# SheetMain.net
KiCad netlist of a schematic drawn in Altium Designer
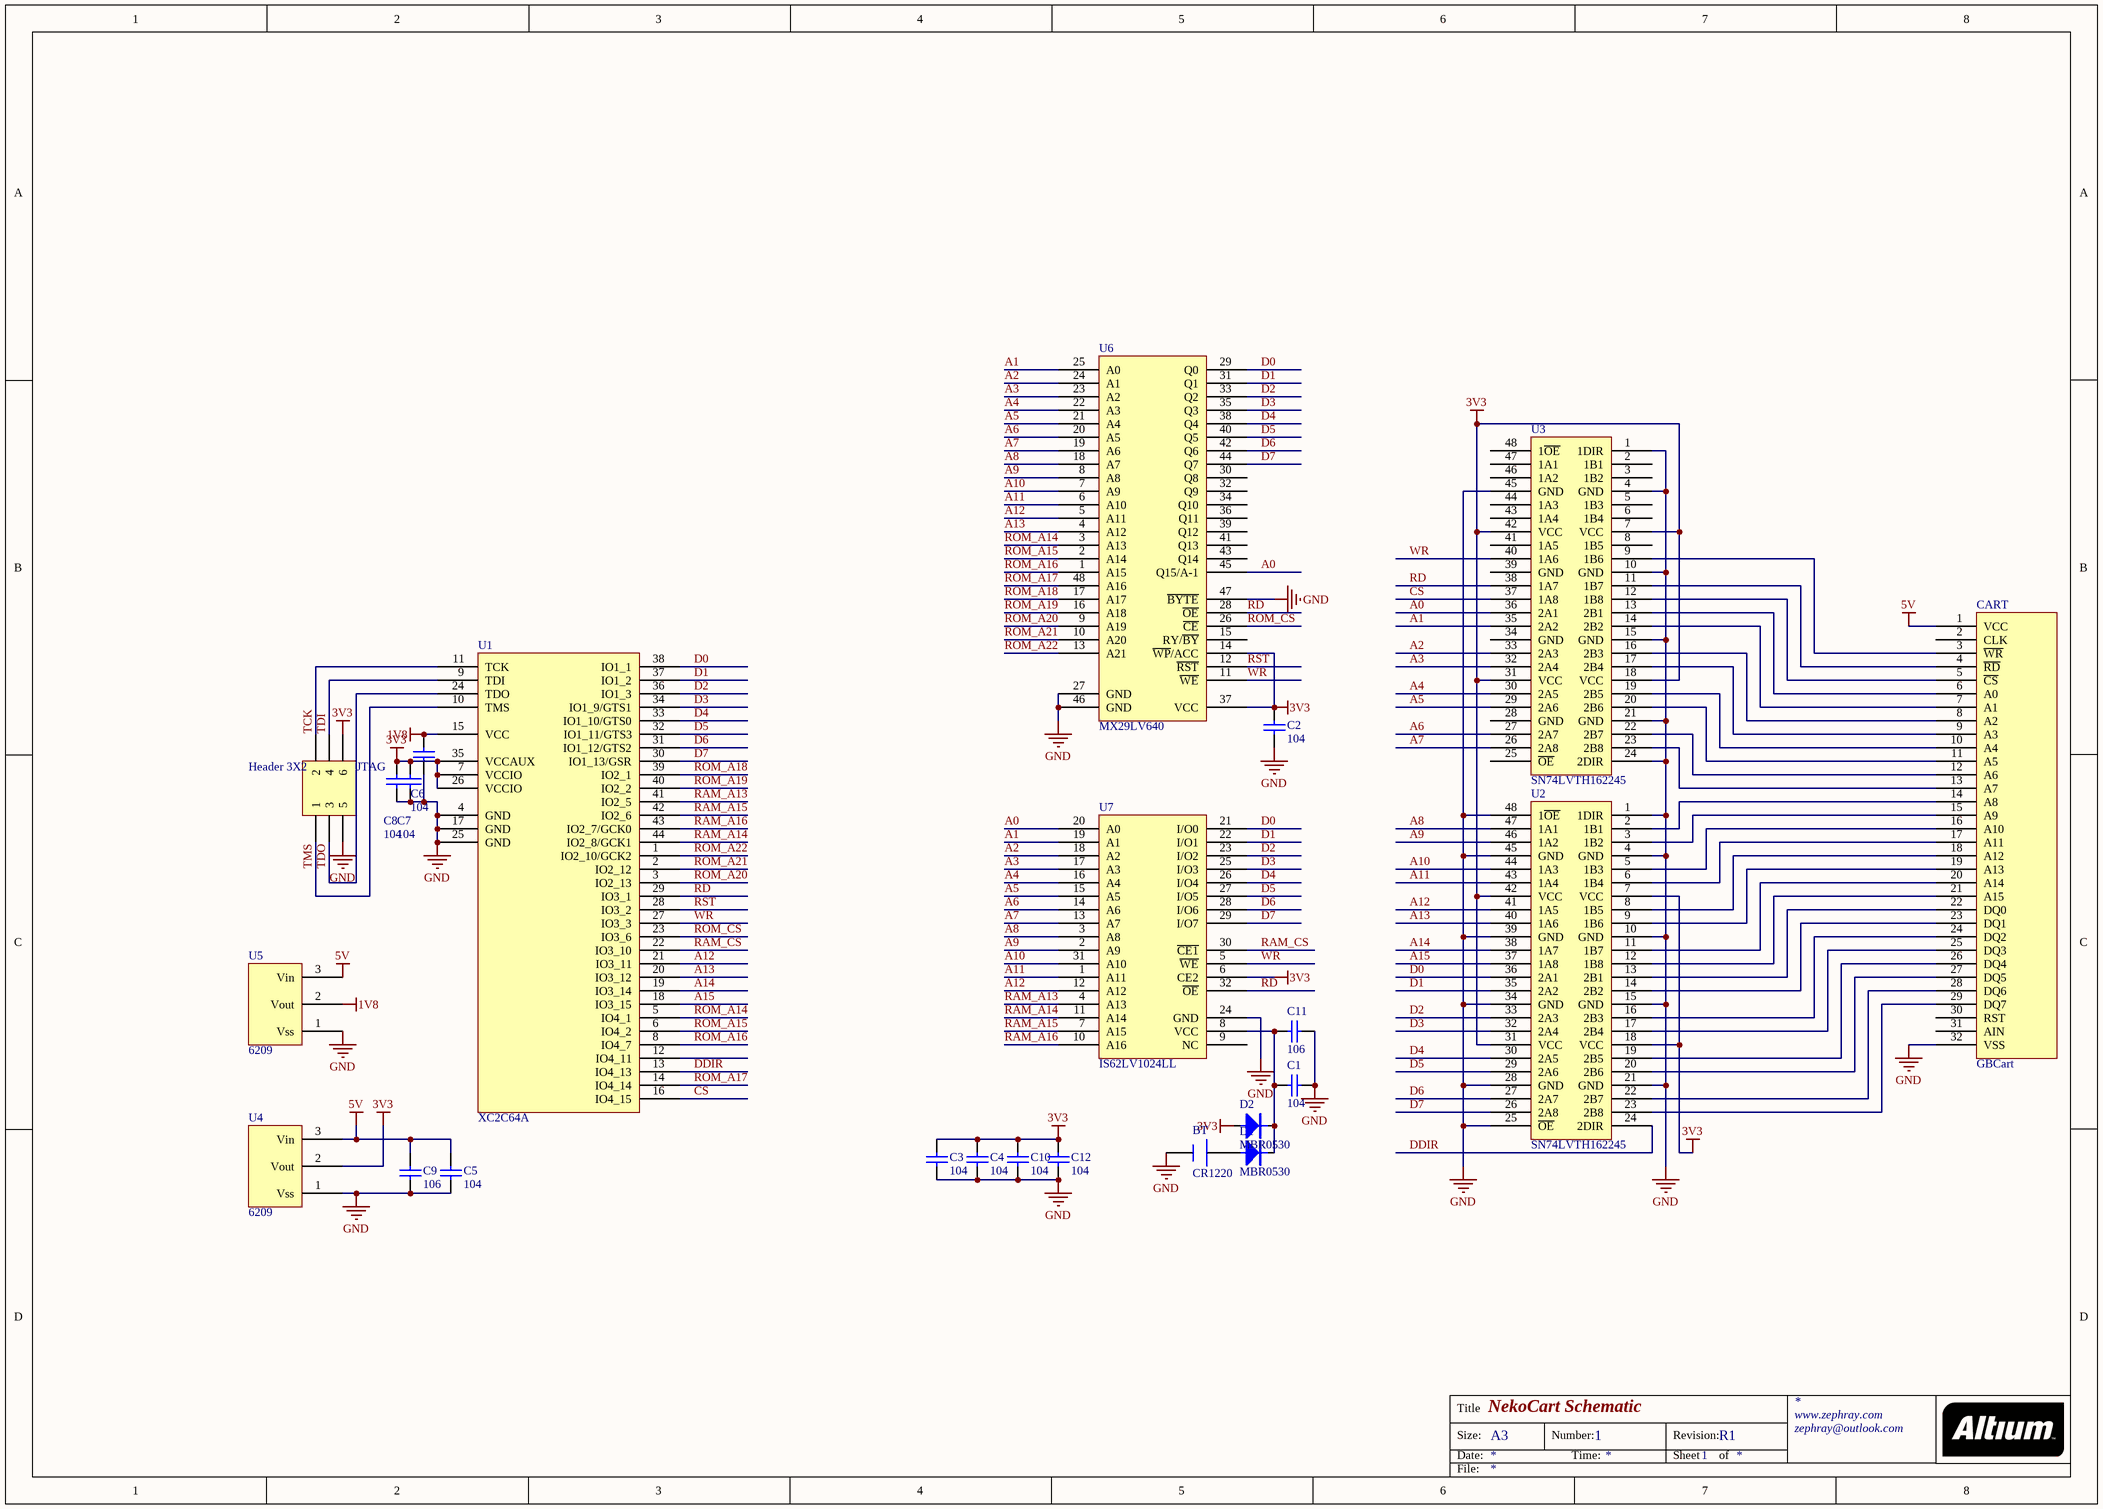
[diagram p0: SheetMain.SchDoc]

(export (version "E")
  (design (tool "Eeschema 10.0.6"))
  (components
    (comp (ref "BT")
      (value "CR1220")
      (footprint "CR1220_socket")
      (fields (field (name "PUBLISHER") "Altium Limited"))
      (libsource (lib "Schlib2") (part "CR1220"))
    )
    (comp (ref "C1")
      (value "104")
      (footprint "1608[0603]")
      (description "Capacitor (Semiconductor SIM Model)")
      (fields (field (name "PUBLISHER") "Altium Limited"))
      (libsource (lib "Miscellaneous Devices") (part "Cap Semi"))
    )
    (comp (ref "C2")
      (value "104")
      (footprint "1608[0603]")
      (description "Capacitor (Semiconductor SIM Model)")
      (fields (field (name "PUBLISHER") "Altium Limited"))
      (libsource (lib "Miscellaneous Devices") (part "Cap Semi"))
    )
    (comp (ref "C3")
      (value "104")
      (footprint "1608[0603]")
      (description "Capacitor (Semiconductor SIM Model)")
      (fields (field (name "PUBLISHER") "Altium Limited"))
      (libsource (lib "Miscellaneous Devices") (part "Cap Semi"))
    )
    (comp (ref "C4")
      (value "104")
      (footprint "1608[0603]")
      (description "Capacitor (Semiconductor SIM Model)")
      (fields (field (name "PUBLISHER") "Altium Limited"))
      (libsource (lib "Miscellaneous Devices") (part "Cap Semi"))
    )
    (comp (ref "C5")
      (value "104")
      (footprint "1608[0603]")
      (description "Capacitor (Semiconductor SIM Model)")
      (fields (field (name "PUBLISHER") "Altium Limited"))
      (libsource (lib "Miscellaneous Devices") (part "Cap Semi"))
    )
    (comp (ref "C6")
      (value "104")
      (footprint "1608[0603]")
      (description "Capacitor (Semiconductor SIM Model)")
      (fields (field (name "PUBLISHER") "Altium Limited"))
      (libsource (lib "Miscellaneous Devices") (part "Cap Semi"))
    )
    (comp (ref "C7")
      (value "104")
      (footprint "1608[0603]")
      (description "Capacitor (Semiconductor SIM Model)")
      (fields (field (name "PUBLISHER") "Altium Limited"))
      (libsource (lib "Miscellaneous Devices") (part "Cap Semi"))
    )
    (comp (ref "C8")
      (value "104")
      (footprint "1608[0603]")
      (description "Capacitor (Semiconductor SIM Model)")
      (fields (field (name "PUBLISHER") "Altium Limited"))
      (libsource (lib "Miscellaneous Devices") (part "Cap Semi"))
    )
    (comp (ref "C9")
      (value "106")
      (footprint "C0805")
      (description "Capacitor (Semiconductor SIM Model)")
      (fields (field (name "PUBLISHER") "Altium Limited"))
      (libsource (lib "Miscellaneous Devices") (part "Cap Semi"))
    )
    (comp (ref "C10")
      (value "104")
      (footprint "1608[0603]")
      (description "Capacitor (Semiconductor SIM Model)")
      (fields (field (name "PUBLISHER") "Altium Limited"))
      (libsource (lib "Miscellaneous Devices") (part "Cap Semi"))
    )
    (comp (ref "C11")
      (value "106")
      (footprint "C0805")
      (description "Capacitor (Semiconductor SIM Model)")
      (fields (field (name "PUBLISHER") "Altium Limited"))
      (libsource (lib "Miscellaneous Devices") (part "Cap Semi"))
    )
    (comp (ref "C12")
      (value "104")
      (footprint "1608[0603]")
      (description "Capacitor (Semiconductor SIM Model)")
      (fields (field (name "PUBLISHER") "Altium Limited"))
      (libsource (lib "Miscellaneous Devices") (part "Cap Semi"))
    )
    (comp (ref "CART") (value "GBCart") (footprint "GB_CART") (libsource (lib "Schlib1") (part "GBCart")))
    (comp (ref "D1") (value "MBR0530") (footprint "0805D") (libsource (lib "Schlib1") (part "1N4148")))
    (comp (ref "D2") (value "MBR0530") (footprint "0805D") (libsource (lib "Schlib1") (part "1N4148")))
    (comp (ref "JTAG")
      (value "Header 3X2")
      (footprint "HDR2X3")
      (description "Header, 3-Pin, Dual row")
      (fields (field (name "PUBLISHER") "Altium Limited"))
      (libsource (lib "Miscellaneous Connectors") (part "Header 3X2"))
    )
    (comp (ref "U1") (value "XC2C64A") (footprint "44A_L") (libsource (lib "Schlib1") (part "XC2C64A")))
    (comp (ref "U2")
      (value "SN74LVTH162245")
      (footprint "TSOP48")
      (libsource (lib "Schlib1") (part "SN74LVTH162245"))
    )
    (comp (ref "U3")
      (value "SN74LVTH162245")
      (footprint "TSOP48")
      (libsource (lib "Schlib1") (part "SN74LVTH162245"))
    )
    (comp (ref "U4") (value "6209") (footprint "SOT-23") (libsource (lib "Schlib1") (part "6209")))
    (comp (ref "U5") (value "6209") (footprint "SOT-23") (libsource (lib "Schlib1") (part "6209")))
    (comp (ref "U6") (value "MX29LV640") (footprint "TSOP48L") (libsource (lib "Schlib1") (part "MX29LV640")))
    (comp (ref "U7")
      (value "IS62LV1024LL")
      (footprint "TSOP32")
      (libsource (lib "Schlib1") (part "IS62LV1024LL"))
    )
  )
  (nets
    (net (code "1") (name "/A0") (class "Default")
      (node (ref "U3") (pin "36") (pinfunction "2A1_36") (pintype "passive"))
      (node (ref "U6") (pin "45") (pinfunction "Q15/A-1_45") (pintype "passive"))
      (node (ref "U7") (pin "20") (pinfunction "A0_20") (pintype "passive"))
    )
    (net (code "2") (name "/A1") (class "Default")
      (node (ref "U3") (pin "35") (pinfunction "2A2_35") (pintype "passive"))
      (node (ref "U6") (pin "25") (pinfunction "A0_25") (pintype "passive"))
      (node (ref "U7") (pin "19") (pinfunction "A1_19") (pintype "passive"))
    )
    (net (code "3") (name "/A2") (class "Default")
      (node (ref "U3") (pin "33") (pinfunction "2A3_33") (pintype "passive"))
      (node (ref "U6") (pin "24") (pinfunction "A1_24") (pintype "passive"))
      (node (ref "U7") (pin "18") (pinfunction "A2_18") (pintype "passive"))
    )
    (net (code "4") (name "/A3") (class "Default")
      (node (ref "U3") (pin "32") (pinfunction "2A4_32") (pintype "passive"))
      (node (ref "U6") (pin "23") (pinfunction "A2_23") (pintype "passive"))
      (node (ref "U7") (pin "17") (pinfunction "A3_17") (pintype "passive"))
    )
    (net (code "5") (name "/A4") (class "Default")
      (node (ref "U3") (pin "30") (pinfunction "2A5_30") (pintype "passive"))
      (node (ref "U6") (pin "22") (pinfunction "A3_22") (pintype "passive"))
      (node (ref "U7") (pin "16") (pinfunction "A4_16") (pintype "passive"))
    )
    (net (code "6") (name "/A5") (class "Default")
      (node (ref "U3") (pin "29") (pinfunction "2A6_29") (pintype "passive"))
      (node (ref "U6") (pin "21") (pinfunction "A4_21") (pintype "passive"))
      (node (ref "U7") (pin "15") (pinfunction "A5_15") (pintype "passive"))
    )
    (net (code "7") (name "/A6") (class "Default")
      (node (ref "U3") (pin "27") (pinfunction "2A7_27") (pintype "passive"))
      (node (ref "U6") (pin "20") (pinfunction "A5_20") (pintype "passive"))
      (node (ref "U7") (pin "14") (pinfunction "A6_14") (pintype "passive"))
    )
    (net (code "8") (name "/A7") (class "Default")
      (node (ref "U3") (pin "26") (pinfunction "2A8_26") (pintype "passive"))
      (node (ref "U6") (pin "19") (pinfunction "A6_19") (pintype "passive"))
      (node (ref "U7") (pin "13") (pinfunction "A7_13") (pintype "passive"))
    )
    (net (code "9") (name "/A8") (class "Default")
      (node (ref "U2") (pin "47") (pinfunction "1A1_47") (pintype "passive"))
      (node (ref "U6") (pin "18") (pinfunction "A7_18") (pintype "passive"))
      (node (ref "U7") (pin "3") (pinfunction "A8_3") (pintype "passive"))
    )
    (net (code "10") (name "/A9") (class "Default")
      (node (ref "U2") (pin "46") (pinfunction "1A2_46") (pintype "passive"))
      (node (ref "U6") (pin "8") (pinfunction "A8_8") (pintype "passive"))
      (node (ref "U7") (pin "2") (pinfunction "A9_2") (pintype "passive"))
    )
    (net (code "11") (name "/A10") (class "Default")
      (node (ref "U2") (pin "44") (pinfunction "1A3_44") (pintype "passive"))
      (node (ref "U6") (pin "7") (pinfunction "A9_7") (pintype "passive"))
      (node (ref "U7") (pin "31") (pinfunction "A10_31") (pintype "passive"))
    )
    (net (code "12") (name "/A11") (class "Default")
      (node (ref "U2") (pin "43") (pinfunction "1A4_43") (pintype "passive"))
      (node (ref "U6") (pin "6") (pinfunction "A10_6") (pintype "passive"))
      (node (ref "U7") (pin "1") (pinfunction "A11_1") (pintype "passive"))
    )
    (net (code "13") (name "/A12") (class "Default")
      (node (ref "U1") (pin "21") (pinfunction "IO3_11_21") (pintype "passive"))
      (node (ref "U2") (pin "41") (pinfunction "1A5_41") (pintype "passive"))
      (node (ref "U6") (pin "5") (pinfunction "A11_5") (pintype "passive"))
      (node (ref "U7") (pin "12") (pinfunction "A12_12") (pintype "passive"))
    )
    (net (code "14") (name "/A13") (class "Default")
      (node (ref "U1") (pin "20") (pinfunction "IO3_12_20") (pintype "passive"))
      (node (ref "U2") (pin "40") (pinfunction "1A6_40") (pintype "passive"))
      (node (ref "U6") (pin "4") (pinfunction "A12_4") (pintype "passive"))
    )
    (net (code "15") (name "/A14") (class "Default")
      (node (ref "U1") (pin "19") (pinfunction "IO3_14_19") (pintype "passive"))
      (node (ref "U2") (pin "38") (pinfunction "1A7_38") (pintype "passive"))
    )
    (net (code "16") (name "/A15") (class "Default")
      (node (ref "U1") (pin "18") (pinfunction "IO3_15_18") (pintype "passive"))
      (node (ref "U2") (pin "37") (pinfunction "1A8_37") (pintype "passive"))
    )
    (net (code "17") (name "/CS") (class "Default")
      (node (ref "U1") (pin "16") (pinfunction "IO4_15_16") (pintype "passive"))
      (node (ref "U3") (pin "37") (pinfunction "1A8_37") (pintype "passive"))
    )
    (net (code "18") (name "/D0") (class "Default")
      (node (ref "U1") (pin "38") (pinfunction "IO1_1_38") (pintype "passive"))
      (node (ref "U2") (pin "36") (pinfunction "2A1_36") (pintype "passive"))
      (node (ref "U6") (pin "29") (pinfunction "Q0_29") (pintype "passive"))
      (node (ref "U7") (pin "21") (pinfunction "I/O0_21") (pintype "passive"))
    )
    (net (code "19") (name "/D1") (class "Default")
      (node (ref "U1") (pin "37") (pinfunction "IO1_2_37") (pintype "passive"))
      (node (ref "U2") (pin "35") (pinfunction "2A2_35") (pintype "passive"))
      (node (ref "U6") (pin "31") (pinfunction "Q1_31") (pintype "passive"))
      (node (ref "U7") (pin "22") (pinfunction "I/O1_22") (pintype "passive"))
    )
    (net (code "20") (name "/D2") (class "Default")
      (node (ref "U1") (pin "36") (pinfunction "IO1_3_36") (pintype "passive"))
      (node (ref "U2") (pin "33") (pinfunction "2A3_33") (pintype "passive"))
      (node (ref "U6") (pin "33") (pinfunction "Q2_33") (pintype "passive"))
      (node (ref "U7") (pin "23") (pinfunction "I/O2_23") (pintype "passive"))
    )
    (net (code "21") (name "/D3") (class "Default")
      (node (ref "U1") (pin "34") (pinfunction "IO1_9/GTS1_34") (pintype "passive"))
      (node (ref "U2") (pin "32") (pinfunction "2A4_32") (pintype "passive"))
      (node (ref "U6") (pin "35") (pinfunction "Q3_35") (pintype "passive"))
      (node (ref "U7") (pin "25") (pinfunction "I/O3_25") (pintype "passive"))
    )
    (net (code "22") (name "/D4") (class "Default")
      (node (ref "U1") (pin "33") (pinfunction "IO1_10/GTS0_33") (pintype "passive"))
      (node (ref "U2") (pin "30") (pinfunction "2A5_30") (pintype "passive"))
      (node (ref "U6") (pin "38") (pinfunction "Q4_38") (pintype "passive"))
      (node (ref "U7") (pin "26") (pinfunction "I/O4_26") (pintype "passive"))
    )
    (net (code "23") (name "/D5") (class "Default")
      (node (ref "U1") (pin "32") (pinfunction "IO1_11/GTS3_32") (pintype "passive"))
      (node (ref "U2") (pin "29") (pinfunction "2A6_29") (pintype "passive"))
      (node (ref "U6") (pin "40") (pinfunction "Q5_40") (pintype "passive"))
      (node (ref "U7") (pin "27") (pinfunction "I/O5_27") (pintype "passive"))
    )
    (net (code "24") (name "/D6") (class "Default")
      (node (ref "U1") (pin "31") (pinfunction "IO1_12/GTS2_31") (pintype "passive"))
      (node (ref "U2") (pin "27") (pinfunction "2A7_27") (pintype "passive"))
      (node (ref "U6") (pin "42") (pinfunction "Q6_42") (pintype "passive"))
      (node (ref "U7") (pin "28") (pinfunction "I/O6_28") (pintype "passive"))
    )
    (net (code "25") (name "/D7") (class "Default")
      (node (ref "U1") (pin "30") (pinfunction "IO1_13/GSR_30") (pintype "passive"))
      (node (ref "U2") (pin "26") (pinfunction "2A8_26") (pintype "passive"))
      (node (ref "U6") (pin "44") (pinfunction "Q7_44") (pintype "passive"))
      (node (ref "U7") (pin "29") (pinfunction "I/O7_29") (pintype "passive"))
    )
    (net (code "26") (name "/DDIR") (class "Default")
      (node (ref "U1") (pin "13") (pinfunction "IO4_13_13") (pintype "passive"))
      (node (ref "U2") (pin "24") (pinfunction "2DIR_24") (pintype "passive"))
    )
    (net (code "27") (name "/RAM_A13") (class "Default")
      (node (ref "U1") (pin "41") (pinfunction "IO2_5_41") (pintype "passive"))
      (node (ref "U7") (pin "4") (pinfunction "A13_4") (pintype "passive"))
    )
    (net (code "28") (name "/RAM_A14") (class "Default")
      (node (ref "U1") (pin "44") (pinfunction "IO2_8/GCK1_44") (pintype "passive"))
      (node (ref "U7") (pin "11") (pinfunction "A14_11") (pintype "passive"))
    )
    (net (code "29") (name "/RAM_A15") (class "Default")
      (node (ref "U1") (pin "42") (pinfunction "IO2_6_42") (pintype "passive"))
      (node (ref "U7") (pin "7") (pinfunction "A15_7") (pintype "passive"))
    )
    (net (code "30") (name "/RAM_A16") (class "Default")
      (node (ref "U1") (pin "43") (pinfunction "IO2_7/GCK0_43") (pintype "passive"))
      (node (ref "U7") (pin "10") (pinfunction "A16_10") (pintype "passive"))
    )
    (net (code "31") (name "/RAM_CS") (class "Default")
      (node (ref "U1") (pin "22") (pinfunction "IO3_10_22") (pintype "passive"))
      (node (ref "U7") (pin "30") (pinfunction "~{CE1}_30") (pintype "passive"))
    )
    (net (code "32") (name "/RD") (class "Default")
      (node (ref "U1") (pin "29") (pinfunction "IO3_1_29") (pintype "passive"))
      (node (ref "U3") (pin "38") (pinfunction "1A7_38") (pintype "passive"))
      (node (ref "U6") (pin "28") (pinfunction "~{OE}_28") (pintype "passive"))
      (node (ref "U7") (pin "32") (pinfunction "~{OE}_32") (pintype "passive"))
    )
    (net (code "33") (name "/ROM_A14") (class "Default")
      (node (ref "U1") (pin "5") (pinfunction "IO4_1_5") (pintype "passive"))
      (node (ref "U6") (pin "3") (pinfunction "A13_3") (pintype "passive"))
    )
    (net (code "34") (name "/ROM_A15") (class "Default")
      (node (ref "U1") (pin "6") (pinfunction "IO4_2_6") (pintype "passive"))
      (node (ref "U6") (pin "2") (pinfunction "A14_2") (pintype "passive"))
    )
    (net (code "35") (name "/ROM_A16") (class "Default")
      (node (ref "U1") (pin "8") (pinfunction "IO4_7_8") (pintype "passive"))
      (node (ref "U6") (pin "1") (pinfunction "A15_1") (pintype "passive"))
    )
    (net (code "36") (name "/ROM_A17") (class "Default")
      (node (ref "U1") (pin "14") (pinfunction "IO4_14_14") (pintype "passive"))
      (node (ref "U6") (pin "48") (pinfunction "A16_48") (pintype "passive"))
    )
    (net (code "37") (name "/ROM_A18") (class "Default")
      (node (ref "U1") (pin "39") (pinfunction "IO2_1_39") (pintype "passive"))
      (node (ref "U6") (pin "17") (pinfunction "A17_17") (pintype "passive"))
    )
    (net (code "38") (name "/ROM_A19") (class "Default")
      (node (ref "U1") (pin "40") (pinfunction "IO2_2_40") (pintype "passive"))
      (node (ref "U6") (pin "16") (pinfunction "A18_16") (pintype "passive"))
    )
    (net (code "39") (name "/ROM_A20") (class "Default")
      (node (ref "U1") (pin "3") (pinfunction "IO2_13_3") (pintype "passive"))
      (node (ref "U6") (pin "9") (pinfunction "A19_9") (pintype "passive"))
    )
    (net (code "40") (name "/ROM_A21") (class "Default")
      (node (ref "U1") (pin "2") (pinfunction "IO2_12_2") (pintype "passive"))
      (node (ref "U6") (pin "10") (pinfunction "A20_10") (pintype "passive"))
    )
    (net (code "41") (name "/ROM_A22") (class "Default")
      (node (ref "U1") (pin "1") (pinfunction "IO2_10/GCK2_1") (pintype "passive"))
      (node (ref "U6") (pin "13") (pinfunction "A21_13") (pintype "passive"))
    )
    (net (code "42") (name "/ROM_CS") (class "Default")
      (node (ref "U1") (pin "23") (pinfunction "IO3_6_23") (pintype "passive"))
      (node (ref "U6") (pin "26") (pinfunction "~{CE}_26") (pintype "passive"))
    )
    (net (code "43") (name "/RST") (class "Default")
      (node (ref "U1") (pin "28") (pinfunction "IO3_2_28") (pintype "passive"))
      (node (ref "U6") (pin "12") (pinfunction "~{RST}_12") (pintype "passive"))
    )
    (net (code "44") (name "/TCK") (class "Default")
      (node (ref "JTAG") (pin "2") (pinfunction "2_2") (pintype "passive"))
      (node (ref "U1") (pin "11") (pinfunction "TCK_11") (pintype "passive"))
    )
    (net (code "45") (name "/TDI") (class "Default")
      (node (ref "JTAG") (pin "4") (pinfunction "4_4") (pintype "passive"))
      (node (ref "U1") (pin "9") (pinfunction "TDI_9") (pintype "passive"))
    )
    (net (code "46") (name "/TDO") (class "Default")
      (node (ref "JTAG") (pin "3") (pinfunction "3_3") (pintype "passive"))
      (node (ref "U1") (pin "24") (pinfunction "TDO_24") (pintype "passive"))
    )
    (net (code "47") (name "/TMS") (class "Default")
      (node (ref "JTAG") (pin "1") (pinfunction "1_1") (pintype "passive"))
      (node (ref "U1") (pin "10") (pinfunction "TMS_10") (pintype "passive"))
    )
    (net (code "48") (name "/WR") (class "Default")
      (node (ref "U1") (pin "27") (pinfunction "IO3_3_27") (pintype "passive"))
      (node (ref "U3") (pin "40") (pinfunction "1A6_40") (pintype "passive"))
      (node (ref "U6") (pin "11") (pinfunction "~{WE}_11") (pintype "passive"))
      (node (ref "U7") (pin "5") (pinfunction "~{WE}_5") (pintype "passive"))
    )
    (net (code "49") (name "1V8") (class "Default")
      (node (ref "C6") (pin "2") (pinfunction "2_2") (pintype "passive"))
      (node (ref "U1") (pin "15") (pinfunction "VCC_15") (pintype "passive"))
      (node (ref "U5") (pin "2") (pinfunction "Vout_2") (pintype "passive"))
    )
    (net (code "50") (name "3V3") (class "Default")
      (node (ref "C10") (pin "1") (pinfunction "1_1") (pintype "passive"))
      (node (ref "C12") (pin "2") (pinfunction "2_2") (pintype "passive"))
      (node (ref "C2") (pin "2") (pinfunction "2_2") (pintype "passive"))
      (node (ref "C3") (pin "2") (pinfunction "2_2") (pintype "passive"))
      (node (ref "C4") (pin "2") (pinfunction "2_2") (pintype "passive"))
      (node (ref "C7") (pin "2") (pinfunction "2_2") (pintype "passive"))
      (node (ref "C8") (pin "2") (pinfunction "2_2") (pintype "passive"))
      (node (ref "D2") (pin "A") (pinfunction "1_A") (pintype "passive"))
      (node (ref "JTAG") (pin "6") (pinfunction "6_6") (pintype "passive"))
      (node (ref "U1") (pin "26") (pinfunction "VCCIO_26") (pintype "passive"))
      (node (ref "U1") (pin "35") (pinfunction "VCCAUX_35") (pintype "passive"))
      (node (ref "U1") (pin "7") (pinfunction "VCCIO_7") (pintype "passive"))
      (node (ref "U2") (pin "18") (pinfunction "VCC_18") (pintype "passive"))
      (node (ref "U2") (pin "31") (pinfunction "VCC_31") (pintype "passive"))
      (node (ref "U2") (pin "42") (pinfunction "VCC_42") (pintype "passive"))
      (node (ref "U2") (pin "7") (pinfunction "VCC_7") (pintype "passive"))
      (node (ref "U3") (pin "18") (pinfunction "VCC_18") (pintype "passive"))
      (node (ref "U3") (pin "31") (pinfunction "VCC_31") (pintype "passive"))
      (node (ref "U3") (pin "42") (pinfunction "VCC_42") (pintype "passive"))
      (node (ref "U3") (pin "7") (pinfunction "VCC_7") (pintype "passive"))
      (node (ref "U4") (pin "2") (pinfunction "Vout_2") (pintype "passive"))
      (node (ref "U6") (pin "14") (pinfunction "~{WP}/ACC_14") (pintype "passive"))
      (node (ref "U6") (pin "37") (pinfunction "VCC_37") (pintype "passive"))
      (node (ref "U7") (pin "6") (pinfunction "CE2_6") (pintype "passive"))
    )
    (net (code "51") (name "5V") (class "Default")
      (node (ref "C5") (pin "2") (pinfunction "2_2") (pintype "passive"))
      (node (ref "C9") (pin "2") (pinfunction "2_2") (pintype "passive"))
      (node (ref "CART") (pin "1") (pinfunction "VCC_1") (pintype "passive"))
      (node (ref "U4") (pin "3") (pinfunction "Vin_3") (pintype "passive"))
      (node (ref "U5") (pin "3") (pinfunction "Vin_3") (pintype "passive"))
    )
    (net (code "52") (name "GND") (class "Default")
      (node (ref "BT") (pin "2") (pinfunction "-_2") (pintype "passive"))
      (node (ref "C1") (pin "1") (pinfunction "1_1") (pintype "passive"))
      (node (ref "C10") (pin "2") (pinfunction "2_2") (pintype "passive"))
      (node (ref "C11") (pin "1") (pinfunction "1_1") (pintype "passive"))
      (node (ref "C12") (pin "1") (pinfunction "1_1") (pintype "passive"))
      (node (ref "C2") (pin "1") (pinfunction "1_1") (pintype "passive"))
      (node (ref "C3") (pin "1") (pinfunction "1_1") (pintype "passive"))
      (node (ref "C4") (pin "1") (pinfunction "1_1") (pintype "passive"))
      (node (ref "C5") (pin "1") (pinfunction "1_1") (pintype "passive"))
      (node (ref "C6") (pin "1") (pinfunction "1_1") (pintype "passive"))
      (node (ref "C7") (pin "1") (pinfunction "1_1") (pintype "passive"))
      (node (ref "C8") (pin "1") (pinfunction "1_1") (pintype "passive"))
      (node (ref "C9") (pin "1") (pinfunction "1_1") (pintype "passive"))
      (node (ref "CART") (pin "32") (pinfunction "VSS_32") (pintype "passive"))
      (node (ref "JTAG") (pin "5") (pinfunction "5_5") (pintype "passive"))
      (node (ref "U1") (pin "17") (pinfunction "GND_17") (pintype "passive"))
      (node (ref "U1") (pin "25") (pinfunction "GND_25") (pintype "passive"))
      (node (ref "U1") (pin "4") (pinfunction "GND_4") (pintype "passive"))
      (node (ref "U2") (pin "1") (pinfunction "1DIR_1") (pintype "passive"))
      (node (ref "U2") (pin "10") (pinfunction "GND_10") (pintype "passive"))
      (node (ref "U2") (pin "15") (pinfunction "GND_15") (pintype "passive"))
      (node (ref "U2") (pin "21") (pinfunction "GND_21") (pintype "passive"))
      (node (ref "U2") (pin "25") (pinfunction "~{OE}_25") (pintype "passive"))
      (node (ref "U2") (pin "28") (pinfunction "GND_28") (pintype "passive"))
      (node (ref "U2") (pin "34") (pinfunction "GND_34") (pintype "passive"))
      (node (ref "U2") (pin "39") (pinfunction "GND_39") (pintype "passive"))
      (node (ref "U2") (pin "4") (pinfunction "GND_4") (pintype "passive"))
      (node (ref "U2") (pin "45") (pinfunction "GND_45") (pintype "passive"))
      (node (ref "U2") (pin "48") (pinfunction "1~{OE}_48") (pintype "passive"))
      (node (ref "U3") (pin "1") (pinfunction "1DIR_1") (pintype "passive"))
      (node (ref "U3") (pin "10") (pinfunction "GND_10") (pintype "passive"))
      (node (ref "U3") (pin "15") (pinfunction "GND_15") (pintype "passive"))
      (node (ref "U3") (pin "21") (pinfunction "GND_21") (pintype "passive"))
      (node (ref "U3") (pin "24") (pinfunction "2DIR_24") (pintype "passive"))
      (node (ref "U3") (pin "4") (pinfunction "GND_4") (pintype "passive"))
      (node (ref "U3") (pin "45") (pinfunction "GND_45") (pintype "passive"))
      (node (ref "U4") (pin "1") (pinfunction "Vss_1") (pintype "passive"))
      (node (ref "U5") (pin "1") (pinfunction "Vss_1") (pintype "passive"))
      (node (ref "U6") (pin "27") (pinfunction "GND_27") (pintype "passive"))
      (node (ref "U6") (pin "46") (pinfunction "GND_46") (pintype "passive"))
      (node (ref "U6") (pin "47") (pinfunction "~{BYTE}_47") (pintype "passive"))
      (node (ref "U7") (pin "24") (pinfunction "GND_24") (pintype "passive"))
    )
    (net (code "53") (name "Net-(BT-+)") (class "Default")
      (node (ref "BT") (pin "1") (pinfunction "+_1") (pintype "passive"))
      (node (ref "D1") (pin "A") (pinfunction "1_A") (pintype "passive"))
    )
    (net (code "54") (name "Net-(CART-A0)") (class "Default")
      (node (ref "CART") (pin "6") (pinfunction "A0_6") (pintype "passive"))
      (node (ref "U3") (pin "13") (pinfunction "2B1_13") (pintype "passive"))
    )
    (net (code "55") (name "Net-(CART-A1)") (class "Default")
      (node (ref "CART") (pin "7") (pinfunction "A1_7") (pintype "passive"))
      (node (ref "U3") (pin "14") (pinfunction "2B2_14") (pintype "passive"))
    )
    (net (code "56") (name "Net-(CART-A2)") (class "Default")
      (node (ref "CART") (pin "8") (pinfunction "A2_8") (pintype "passive"))
      (node (ref "U3") (pin "16") (pinfunction "2B3_16") (pintype "passive"))
    )
    (net (code "57") (name "Net-(CART-A3)") (class "Default")
      (node (ref "CART") (pin "9") (pinfunction "A3_9") (pintype "passive"))
      (node (ref "U3") (pin "17") (pinfunction "2B4_17") (pintype "passive"))
    )
    (net (code "58") (name "Net-(CART-A4)") (class "Default")
      (node (ref "CART") (pin "10") (pinfunction "A4_10") (pintype "passive"))
      (node (ref "U3") (pin "19") (pinfunction "2B5_19") (pintype "passive"))
    )
    (net (code "59") (name "Net-(CART-A5)") (class "Default")
      (node (ref "CART") (pin "11") (pinfunction "A5_11") (pintype "passive"))
      (node (ref "U3") (pin "20") (pinfunction "2B6_20") (pintype "passive"))
    )
    (net (code "60") (name "Net-(CART-A6)") (class "Default")
      (node (ref "CART") (pin "12") (pinfunction "A6_12") (pintype "passive"))
      (node (ref "U3") (pin "22") (pinfunction "2B7_22") (pintype "passive"))
    )
    (net (code "61") (name "Net-(CART-A7)") (class "Default")
      (node (ref "CART") (pin "13") (pinfunction "A7_13") (pintype "passive"))
      (node (ref "U3") (pin "23") (pinfunction "2B8_23") (pintype "passive"))
    )
    (net (code "62") (name "Net-(CART-A8)") (class "Default")
      (node (ref "CART") (pin "14") (pinfunction "A8_14") (pintype "passive"))
      (node (ref "U2") (pin "2") (pinfunction "1B1_2") (pintype "passive"))
    )
    (net (code "63") (name "Net-(CART-A9)") (class "Default")
      (node (ref "CART") (pin "15") (pinfunction "A9_15") (pintype "passive"))
      (node (ref "U2") (pin "3") (pinfunction "1B2_3") (pintype "passive"))
    )
    (net (code "64") (name "Net-(CART-A10)") (class "Default")
      (node (ref "CART") (pin "16") (pinfunction "A10_16") (pintype "passive"))
      (node (ref "U2") (pin "5") (pinfunction "1B3_5") (pintype "passive"))
    )
    (net (code "65") (name "Net-(CART-A11)") (class "Default")
      (node (ref "CART") (pin "17") (pinfunction "A11_17") (pintype "passive"))
      (node (ref "U2") (pin "6") (pinfunction "1B4_6") (pintype "passive"))
    )
    (net (code "66") (name "Net-(CART-A12)") (class "Default")
      (node (ref "CART") (pin "18") (pinfunction "A12_18") (pintype "passive"))
      (node (ref "U2") (pin "8") (pinfunction "1B5_8") (pintype "passive"))
    )
    (net (code "67") (name "Net-(CART-A13)") (class "Default")
      (node (ref "CART") (pin "19") (pinfunction "A13_19") (pintype "passive"))
      (node (ref "U2") (pin "9") (pinfunction "1B6_9") (pintype "passive"))
    )
    (net (code "68") (name "Net-(CART-A14)") (class "Default")
      (node (ref "CART") (pin "20") (pinfunction "A14_20") (pintype "passive"))
      (node (ref "U2") (pin "11") (pinfunction "1B7_11") (pintype "passive"))
    )
    (net (code "69") (name "Net-(CART-A15)") (class "Default")
      (node (ref "CART") (pin "21") (pinfunction "A15_21") (pintype "passive"))
      (node (ref "U2") (pin "12") (pinfunction "1B8_12") (pintype "passive"))
    )
    (net (code "70") (name "Net-(CART-DQ0)") (class "Default")
      (node (ref "CART") (pin "22") (pinfunction "DQ0_22") (pintype "passive"))
      (node (ref "U2") (pin "13") (pinfunction "2B1_13") (pintype "passive"))
    )
    (net (code "71") (name "Net-(CART-DQ1)") (class "Default")
      (node (ref "CART") (pin "23") (pinfunction "DQ1_23") (pintype "passive"))
      (node (ref "U2") (pin "14") (pinfunction "2B2_14") (pintype "passive"))
    )
    (net (code "72") (name "Net-(CART-DQ2)") (class "Default")
      (node (ref "CART") (pin "24") (pinfunction "DQ2_24") (pintype "passive"))
      (node (ref "U2") (pin "16") (pinfunction "2B3_16") (pintype "passive"))
    )
    (net (code "73") (name "Net-(CART-DQ3)") (class "Default")
      (node (ref "CART") (pin "25") (pinfunction "DQ3_25") (pintype "passive"))
      (node (ref "U2") (pin "17") (pinfunction "2B4_17") (pintype "passive"))
    )
    (net (code "74") (name "Net-(CART-DQ4)") (class "Default")
      (node (ref "CART") (pin "26") (pinfunction "DQ4_26") (pintype "passive"))
      (node (ref "U2") (pin "19") (pinfunction "2B5_19") (pintype "passive"))
    )
    (net (code "75") (name "Net-(CART-DQ5)") (class "Default")
      (node (ref "CART") (pin "27") (pinfunction "DQ5_27") (pintype "passive"))
      (node (ref "U2") (pin "20") (pinfunction "2B6_20") (pintype "passive"))
    )
    (net (code "76") (name "Net-(CART-DQ6)") (class "Default")
      (node (ref "CART") (pin "28") (pinfunction "DQ6_28") (pintype "passive"))
      (node (ref "U2") (pin "22") (pinfunction "2B7_22") (pintype "passive"))
    )
    (net (code "77") (name "Net-(CART-DQ7)") (class "Default")
      (node (ref "CART") (pin "29") (pinfunction "DQ7_29") (pintype "passive"))
      (node (ref "U2") (pin "23") (pinfunction "2B8_23") (pintype "passive"))
    )
    (net (code "78") (name "Net-(CART-~{CS})") (class "Default")
      (node (ref "CART") (pin "5") (pinfunction "~{CS}_5") (pintype "passive"))
      (node (ref "U3") (pin "12") (pinfunction "1B8_12") (pintype "passive"))
    )
    (net (code "79") (name "Net-(CART-~{RD})") (class "Default")
      (node (ref "CART") (pin "4") (pinfunction "~{RD}_4") (pintype "passive"))
      (node (ref "U3") (pin "11") (pinfunction "1B7_11") (pintype "passive"))
    )
    (net (code "80") (name "Net-(CART-~{WR})") (class "Default")
      (node (ref "CART") (pin "3") (pinfunction "~{WR}_3") (pintype "passive"))
      (node (ref "U3") (pin "9") (pinfunction "1B6_9") (pintype "passive"))
    )
    (net (code "81") (name "Net-(D1-2)") (class "Default")
      (node (ref "C1") (pin "2") (pinfunction "2_2") (pintype "passive"))
      (node (ref "C11") (pin "2") (pinfunction "2_2") (pintype "passive"))
      (node (ref "D1") (pin "K") (pinfunction "2_K") (pintype "passive"))
      (node (ref "D2") (pin "K") (pinfunction "2_K") (pintype "passive"))
      (node (ref "U7") (pin "8") (pinfunction "VCC_8") (pintype "passive"))
    )
    (net (code "82") (name "unconnected-(CART-AIN-Pad31)") (class "Default")
      (node (ref "CART") (pin "31") (pinfunction "AIN_31") (pintype "passive"))
    )
    (net (code "83") (name "unconnected-(CART-CLK-Pad2)") (class "Default")
      (node (ref "CART") (pin "2") (pinfunction "CLK_2") (pintype "passive"))
    )
    (net (code "84") (name "unconnected-(CART-RST-Pad30)") (class "Default")
      (node (ref "CART") (pin "30") (pinfunction "RST_30") (pintype "passive"))
    )
    (net (code "85") (name "unconnected-(U1-IO4_11-Pad12)") (class "Default")
      (node (ref "U1") (pin "12") (pinfunction "IO4_11_12") (pintype "passive"))
    )
    (net (code "86") (name "unconnected-(U3-1A1-Pad47)") (class "Default")
      (node (ref "U3") (pin "47") (pinfunction "1A1_47") (pintype "passive"))
    )
    (net (code "87") (name "unconnected-(U3-1A2-Pad46)") (class "Default")
      (node (ref "U3") (pin "46") (pinfunction "1A2_46") (pintype "passive"))
    )
    (net (code "88") (name "unconnected-(U3-1A3-Pad44)") (class "Default")
      (node (ref "U3") (pin "44") (pinfunction "1A3_44") (pintype "passive"))
    )
    (net (code "89") (name "unconnected-(U3-1A4-Pad43)") (class "Default")
      (node (ref "U3") (pin "43") (pinfunction "1A4_43") (pintype "passive"))
    )
    (net (code "90") (name "unconnected-(U3-1A5-Pad41)") (class "Default")
      (node (ref "U3") (pin "41") (pinfunction "1A5_41") (pintype "passive"))
    )
    (net (code "91") (name "unconnected-(U3-1B1-Pad2)") (class "Default")
      (node (ref "U3") (pin "2") (pinfunction "1B1_2") (pintype "passive"))
    )
    (net (code "92") (name "unconnected-(U3-1B2-Pad3)") (class "Default")
      (node (ref "U3") (pin "3") (pinfunction "1B2_3") (pintype "passive"))
    )
    (net (code "93") (name "unconnected-(U3-1B3-Pad5)") (class "Default")
      (node (ref "U3") (pin "5") (pinfunction "1B3_5") (pintype "passive"))
    )
    (net (code "94") (name "unconnected-(U3-1B4-Pad6)") (class "Default")
      (node (ref "U3") (pin "6") (pinfunction "1B4_6") (pintype "passive"))
    )
    (net (code "95") (name "unconnected-(U3-1B5-Pad8)") (class "Default")
      (node (ref "U3") (pin "8") (pinfunction "1B5_8") (pintype "passive"))
    )
    (net (code "96") (name "unconnected-(U3-1~{OE}-Pad48)") (class "Default")
      (node (ref "U3") (pin "48") (pinfunction "1~{OE}_48") (pintype "passive"))
    )
    (net (code "97") (name "unconnected-(U3-GND-Pad28)") (class "Default")
      (node (ref "U3") (pin "28") (pinfunction "GND_28") (pintype "passive"))
    )
    (net (code "98") (name "unconnected-(U3-GND-Pad34)") (class "Default")
      (node (ref "U3") (pin "34") (pinfunction "GND_34") (pintype "passive"))
    )
    (net (code "99") (name "unconnected-(U3-GND-Pad39)") (class "Default")
      (node (ref "U3") (pin "39") (pinfunction "GND_39") (pintype "passive"))
    )
    (net (code "100") (name "unconnected-(U3-~{OE}-Pad25)") (class "Default")
      (node (ref "U3") (pin "25") (pinfunction "~{OE}_25") (pintype "passive"))
    )
    (net (code "101") (name "unconnected-(U6-Q8-Pad30)") (class "Default")
      (node (ref "U6") (pin "30") (pinfunction "Q8_30") (pintype "passive"))
    )
    (net (code "102") (name "unconnected-(U6-Q9-Pad32)") (class "Default")
      (node (ref "U6") (pin "32") (pinfunction "Q9_32") (pintype "passive"))
    )
    (net (code "103") (name "unconnected-(U6-Q10-Pad34)") (class "Default")
      (node (ref "U6") (pin "34") (pinfunction "Q10_34") (pintype "passive"))
    )
    (net (code "104") (name "unconnected-(U6-Q11-Pad36)") (class "Default")
      (node (ref "U6") (pin "36") (pinfunction "Q11_36") (pintype "passive"))
    )
    (net (code "105") (name "unconnected-(U6-Q12-Pad39)") (class "Default")
      (node (ref "U6") (pin "39") (pinfunction "Q12_39") (pintype "passive"))
    )
    (net (code "106") (name "unconnected-(U6-Q13-Pad41)") (class "Default")
      (node (ref "U6") (pin "41") (pinfunction "Q13_41") (pintype "passive"))
    )
    (net (code "107") (name "unconnected-(U6-Q14-Pad43)") (class "Default")
      (node (ref "U6") (pin "43") (pinfunction "Q14_43") (pintype "passive"))
    )
    (net (code "108") (name "unconnected-(U6-RY{slash}~{BY}-Pad15)") (class "Default")
      (node (ref "U6") (pin "15") (pinfunction "RY/~{BY}_15") (pintype "passive"))
    )
    (net (code "109") (name "unconnected-(U7-NC-Pad9)") (class "Default")
      (node (ref "U7") (pin "9") (pinfunction "NC_9") (pintype "passive"))
    )
  )
)
